# Voltage_Regulator.net
KiCad netlist of a schematic drawn in Altium Designer
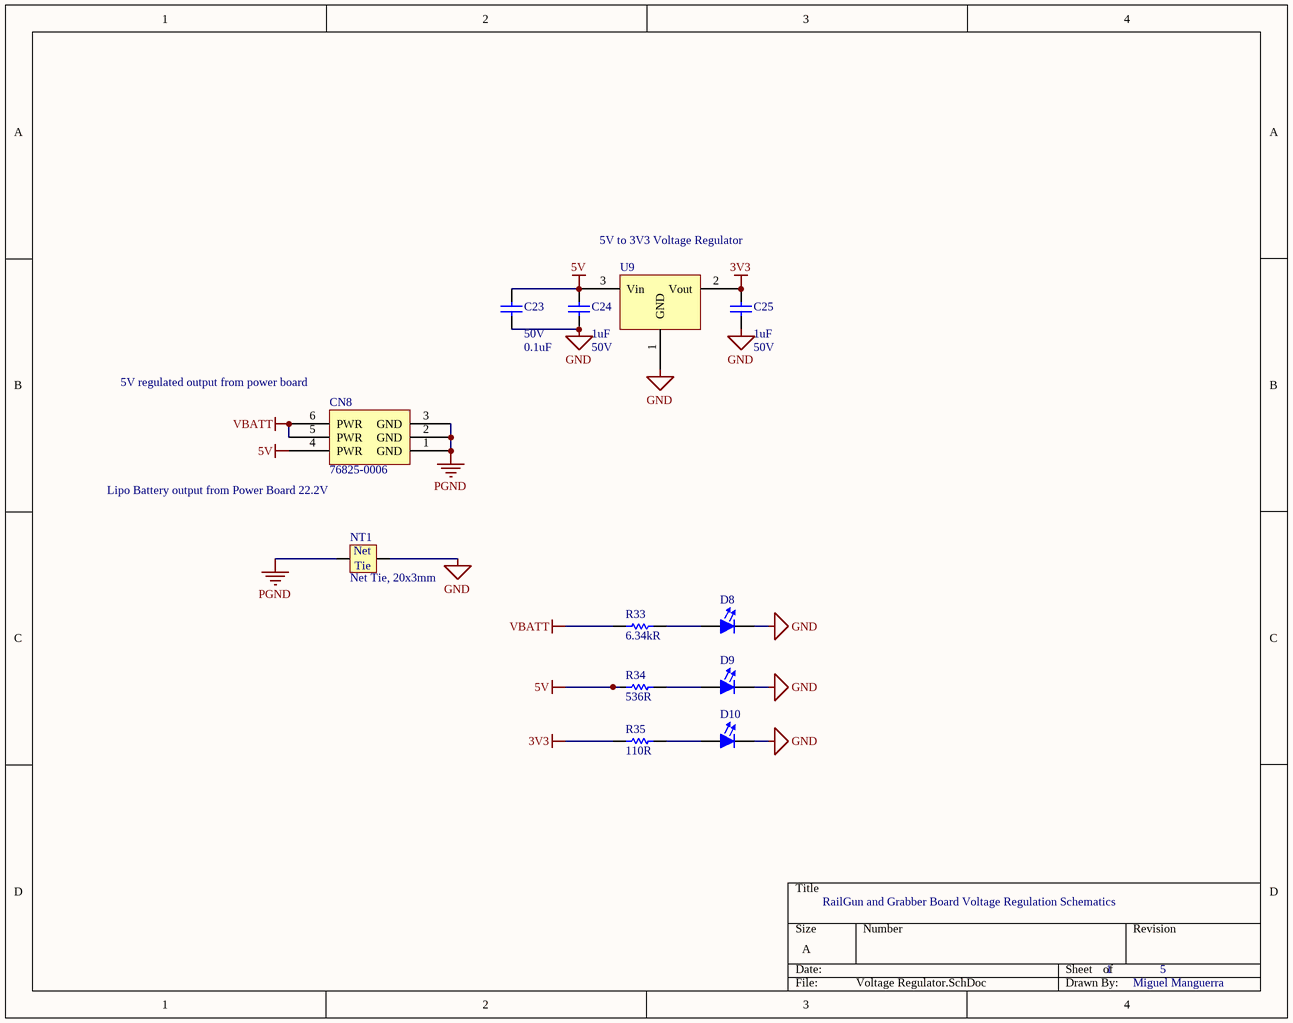
[diagram p0: Voltage Regulator.SchDoc]

(export (version "E")
  (design (tool "Eeschema 10.0.6"))
  (components
    (comp (ref "C23")
      (value "CL10B104JB8NNNC")
      (footprint "FP-CL10-0_1-MFG")
      (description "CAP CER 0.1UF 50V X7R 0603")
      (fields
        (field (name "TOLERANCE") "5%")
        (field (name "VOLTAGE") "50V")
        (field (name "CAPACITANCE") "0.1uF")
      )
      (libsource (lib "AUVIC") (part "CAP-NP-2"))
    )
    (comp (ref "C24")
      (value "CL21B105KBFNNNG")
      (footprint "0803 CAP")
      (description "SAMSUNG ELECTRO-MECHANICS - CL21B105KBFNNNG - MLCC CAPACITORS")
      (fields
        (field (name "TOLERANCE") "10%")
        (field (name "CAPACITANCE") "1uF")
        (field (name "VOLTAGE") "50V")
      )
      (libsource (lib "") (part "Symbol_1"))
    )
    (comp (ref "C25")
      (value "CL21B105KBFNNNG")
      (footprint "0803 CAP")
      (description "SAMSUNG ELECTRO-MECHANICS - CL21B105KBFNNNG - MLCC CAPACITORS")
      (fields
        (field (name "TOLERANCE") "10%")
        (field (name "CAPACITANCE") "1uF")
        (field (name "VOLTAGE") "50V")
      )
      (libsource (lib "") (part "Symbol_1"))
    )
    (comp (ref "CN8")
      (value "76825-0006")
      (footprint "76825-0006-Footprint-1")
      (libsource (lib "AUVIC") (part "76825-0006"))
    )
    (comp (ref "D8")
      (value "LT Q39G-Q1OO-25-1")
      (footprint "FP-LB_Q39E-MFG")
      (description "LED GREEN DIFFUSED 0603 SMD")
      (libsource (lib "") (part "Symbol_2"))
    )
    (comp (ref "D9")
      (value "LT Q39G-Q1OO-25-1")
      (footprint "FP-LB_Q39E-MFG")
      (description "LED GREEN DIFFUSED 0603 SMD")
      (libsource (lib "") (part "Symbol_2"))
    )
    (comp (ref "D10")
      (value "LT Q39G-Q1OO-25-1")
      (footprint "FP-LB_Q39E-MFG")
      (description "LED GREEN DIFFUSED 0603 SMD")
      (libsource (lib "") (part "Symbol_2"))
    )
    (comp (ref "NT1")
      (value "Net Tie, 20x3mm")
      (footprint "NETTIE_20x3mm")
      (fields
        (field (name "SOURCE") "AUVic_Integrated_Library_Virtual_Components.SchLib")
        (field (name "CREATED BY") "Ashwin Sira")
        (field (name "PUBLISHER") "AUVic")
      )
      (libsource (lib "AUVIC") (part "Symbol"))
    )
    (comp (ref "R33")
      (value "6.34kR")
      (footprint "RESC1609X50X30NL10T20")
      (fields (field (name "TOLERANCE") "1%"))
      (libsource (lib "AUVIC") (part "RES"))
    )
    (comp (ref "R34")
      (value "536R")
      (footprint "RESC1608X55X30LL15T15")
      (description "SMD Chip Resistor, 0603 [1608 Metric], 536 ohm, ERJ3EK Series, 75 V, Thick Film, 100 mW")
      (fields (field (name "TOLERANCE") "1%"))
      (libsource (lib "AUVIC") (part "RES"))
    )
    (comp (ref "R35")
      (value "110R")
      (footprint "RESC1608X55X25ML10T15")
      (description "RES SMD 110 OHM 1% 1/10W 0603")
      (fields (field (name "TOLERANCE") "1%"))
      (libsource (lib "AUVIC") (part "RES"))
    )
    (comp (ref "U9")
      (value "3.3V 250mA Linear Reg LDO")
      (footprint "SOT95P245X110-3N")
      (description "IC REG LINEAR 3.3V 250MA SOT23-3")
      (fields (field (name "CREATED BY") "Poorna Chander Kalidas"))
      (libsource (lib "AUVIC") (part "3.3V 250mA Linear Reg LDO"))
    )
  )
  (nets
    (net (code "1") (name "3V3") (class "Default")
      (node (ref "C25") (pin "1") (pinfunction "1_1") (pintype "passive"))
      (node (ref "R35") (pin "1") (pinfunction "1_1") (pintype "passive"))
      (node (ref "U9") (pin "2") (pinfunction "Vout_2") (pintype "power_in"))
    )
    (net (code "2") (name "5V") (class "Default")
      (node (ref "C23") (pin "1") (pinfunction "1_1") (pintype "passive"))
      (node (ref "C24") (pin "1") (pinfunction "1_1") (pintype "passive"))
      (node (ref "CN8") (pin "4") (pinfunction "PWR_4") (pintype "passive"))
      (node (ref "R34") (pin "1") (pinfunction "1_1") (pintype "passive"))
      (node (ref "U9") (pin "3") (pinfunction "Vin_3") (pintype "power_in"))
    )
    (net (code "3") (name "GND") (class "Default")
      (node (ref "C23") (pin "2") (pinfunction "2_2") (pintype "passive"))
      (node (ref "C24") (pin "2") (pinfunction "2_2") (pintype "passive"))
      (node (ref "C25") (pin "2") (pinfunction "2_2") (pintype "passive"))
      (node (ref "D10") (pin "1") (pinfunction "Cathode_1") (pintype "passive"))
      (node (ref "D8") (pin "1") (pinfunction "Cathode_1") (pintype "passive"))
      (node (ref "D9") (pin "1") (pinfunction "Cathode_1") (pintype "passive"))
      (node (ref "NT1") (pin "2") (pinfunction "2_2") (pintype "passive"))
      (node (ref "U9") (pin "1") (pinfunction "GND_1") (pintype "power_in"))
    )
    (net (code "4") (name "Net-(D8-Anode)") (class "Default")
      (node (ref "D8") (pin "2") (pinfunction "Anode_2") (pintype "passive"))
      (node (ref "R33") (pin "2") (pinfunction "2_2") (pintype "passive"))
    )
    (net (code "5") (name "Net-(D9-Anode)") (class "Default")
      (node (ref "D9") (pin "2") (pinfunction "Anode_2") (pintype "passive"))
      (node (ref "R34") (pin "2") (pinfunction "2_2") (pintype "passive"))
    )
    (net (code "6") (name "Net-(D10-Anode)") (class "Default")
      (node (ref "D10") (pin "2") (pinfunction "Anode_2") (pintype "passive"))
      (node (ref "R35") (pin "2") (pinfunction "2_2") (pintype "passive"))
    )
    (net (code "7") (name "PGND") (class "Default")
      (node (ref "CN8") (pin "1") (pinfunction "GND_1") (pintype "passive"))
      (node (ref "CN8") (pin "2") (pinfunction "GND_2") (pintype "passive"))
      (node (ref "CN8") (pin "3") (pinfunction "GND_3") (pintype "passive"))
      (node (ref "NT1") (pin "1") (pinfunction "1_1") (pintype "passive"))
    )
    (net (code "8") (name "VBATT") (class "Default")
      (node (ref "CN8") (pin "5") (pinfunction "PWR_5") (pintype "passive"))
      (node (ref "CN8") (pin "6") (pinfunction "PWR_6") (pintype "passive"))
      (node (ref "R33") (pin "1") (pinfunction "1_1") (pintype "passive"))
    )
  )
)
